# V4-AddOnSduino-V003.net
KiCad netlist of a schematic drawn in EAGLE
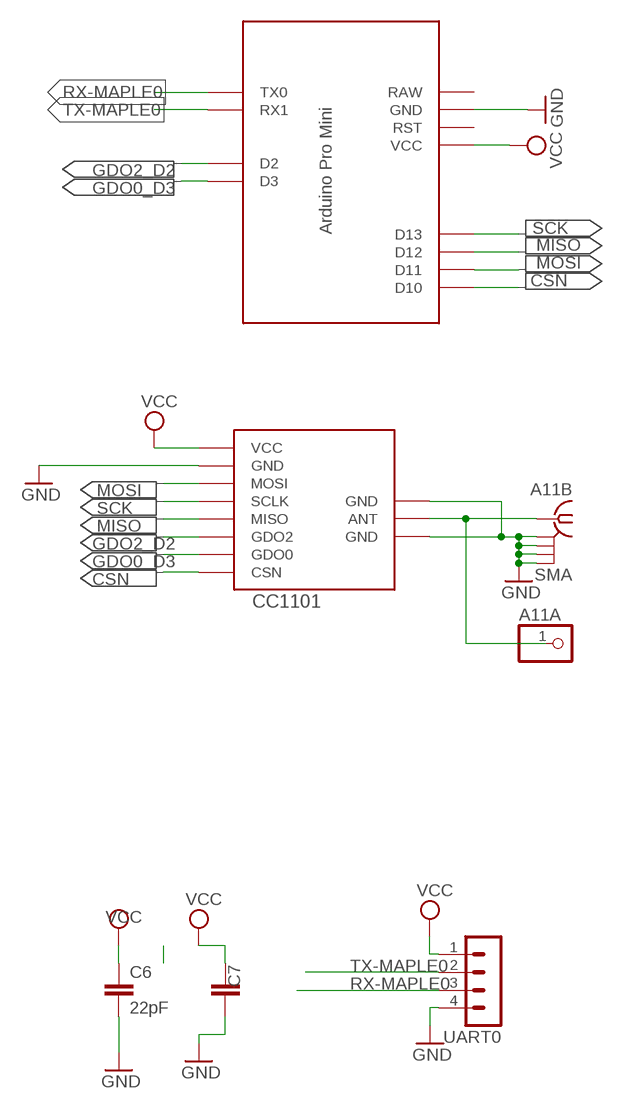
[diagram p0: schematic, sheet 1]

(export (version "E")
  (design (tool "Eeschema 10.0.6"))
  (components
    (comp (ref "A11A")
      (value "PINHD-1X1")
      (footprint "eagle-import:1X01")
      (libsource (lib "eagle-import") (part "PINHD-1X1"))
    )
    (comp (ref "A11B")
      (value "SMA")
      (footprint "eagle-import:SMA")
      (libsource (lib "eagle-import") (part "SMA"))
    )
    (comp (ref "C6")
      (value "22pF")
      (footprint "eagle-import:C0805")
      (libsource (lib "eagle-import") (part "C-EUC0805"))
    )
    (comp (ref "C7")
      (value "C-EUC1812")
      (footprint "eagle-import:C1812")
      (libsource (lib "eagle-import") (part "C-EUC1812"))
    )
    (comp (ref "CC1101")
      (value "CC1101_MODULE1SMD")
      (footprint "eagle-import:CC1101_MODULE1_SMD")
      (libsource (lib "eagle-import") (part "CC1101_MODULE1SMD"))
    )
    (comp (ref "U$2")
      (value "MARTIN-PROMINI-CC1101")
      (footprint "eagle-import:MARTIN-PRO-CC1101")
      (libsource (lib "eagle-import") (part "MARTIN-PROMINI-CC1101"))
    )
    (comp (ref "UART0")
      (value "MA04-1")
      (footprint "eagle-import:MA04-1")
      (libsource (lib "eagle-import") (part "MA04-1"))
    )
  )
  (nets
    (net (code "1") (name "/CSN") (class "Default")
      (node (ref "CC1101") (pin "CSN") (pinfunction "CSN_CSN") (pintype "bidirectional"))
      (node (ref "U$2") (pin "D10") (pinfunction "D10_D10") (pintype "bidirectional"))
    )
    (net (code "2") (name "/GDO0_D3") (class "Default")
      (node (ref "CC1101") (pin "GDO0") (pinfunction "GDO0_GDO0") (pintype "bidirectional"))
      (node (ref "U$2") (pin "D3") (pinfunction "D3_D3") (pintype "bidirectional"))
    )
    (net (code "3") (name "/GDO2_D2") (class "Default")
      (node (ref "CC1101") (pin "GDO2") (pinfunction "GDO2_GDO2") (pintype "bidirectional"))
      (node (ref "U$2") (pin "D2") (pinfunction "D2_D2") (pintype "bidirectional"))
    )
    (net (code "4") (name "/MISO") (class "Default")
      (node (ref "CC1101") (pin "MISO") (pinfunction "MISO_MISO") (pintype "bidirectional"))
      (node (ref "U$2") (pin "D12") (pinfunction "D12_D12") (pintype "bidirectional"))
    )
    (net (code "5") (name "/MOSI") (class "Default")
      (node (ref "CC1101") (pin "MOSI") (pinfunction "MOSI_MOSI") (pintype "bidirectional"))
      (node (ref "U$2") (pin "D11") (pinfunction "D11_D11") (pintype "bidirectional"))
    )
    (net (code "6") (name "/SCK") (class "Default")
      (node (ref "CC1101") (pin "SCLK") (pinfunction "SCLK_SCLK") (pintype "bidirectional"))
      (node (ref "U$2") (pin "D13") (pinfunction "D13_D13") (pintype "bidirectional"))
    )
    (net (code "7") (name "GND") (class "Default")
      (node (ref "A11B") (pin "GND@1") (pinfunction "2_GND@1") (pintype "passive"))
      (node (ref "A11B") (pin "GND@2") (pinfunction "3_GND@2") (pintype "passive"))
      (node (ref "A11B") (pin "GND@3") (pinfunction "4_GND@3") (pintype "passive"))
      (node (ref "A11B") (pin "GND@4") (pinfunction "5_GND@4") (pintype "passive"))
      (node (ref "C6") (pin "2") (pinfunction "2_2") (pintype "passive"))
      (node (ref "C7") (pin "1") (pinfunction "1_1") (pintype "passive"))
      (node (ref "CC1101") (pin "GND@0") (pinfunction "GND_GND@0") (pintype "power_in"))
      (node (ref "CC1101") (pin "GND@1") (pinfunction "GND_GND@1") (pintype "power_in"))
      (node (ref "CC1101") (pin "GND@2") (pinfunction "GND_GND@2") (pintype "power_in"))
      (node (ref "U$2") (pin "GND") (pinfunction "GND_GND") (pintype "bidirectional"))
      (node (ref "UART0") (pin "4") (pinfunction "4_4") (pintype "passive"))
    )
    (net (code "8") (name "Net-(A11A-Pad1)") (class "Default")
      (node (ref "A11A") (pin "1") (pinfunction "1_1") (pintype "passive"))
      (node (ref "A11B") (pin "1") (pinfunction "1_1") (pintype "passive"))
      (node (ref "CC1101") (pin "ANT") (pinfunction "ANT_ANT") (pintype "output"))
    )
    (net (code "9") (name "RX-MAPLE0") (class "Default")
      (node (ref "U$2") (pin "TX0") (pinfunction "TX0_TX0") (pintype "bidirectional"))
      (node (ref "UART0") (pin "3") (pinfunction "3_3") (pintype "passive"))
    )
    (net (code "10") (name "TX-MAPLE0") (class "Default")
      (node (ref "U$2") (pin "RX1") (pinfunction "RX1_RX1") (pintype "bidirectional"))
      (node (ref "UART0") (pin "2") (pinfunction "2_2") (pintype "passive"))
    )
    (net (code "11") (name "VCC") (class "Default")
      (node (ref "C6") (pin "1") (pinfunction "1_1") (pintype "passive"))
      (node (ref "C7") (pin "2") (pinfunction "2_2") (pintype "passive"))
      (node (ref "CC1101") (pin "VCC") (pinfunction "VCC_VCC") (pintype "power_in"))
      (node (ref "U$2") (pin "VCC") (pinfunction "VCC_VCC") (pintype "bidirectional"))
      (node (ref "UART0") (pin "1") (pinfunction "1_1") (pintype "passive"))
    )
    (net (code "12") (name "unconnected-(U$2-PadRAW)") (class "Default")
      (node (ref "U$2") (pin "RAW") (pinfunction "RAW_RAW") (pintype "bidirectional"))
    )
    (net (code "13") (name "unconnected-(U$2-PadRST)") (class "Default")
      (node (ref "U$2") (pin "RST") (pinfunction "RST_RST") (pintype "bidirectional"))
    )
  )
)
